# Sheet1.net
KiCad netlist of a schematic drawn in Altium Designer
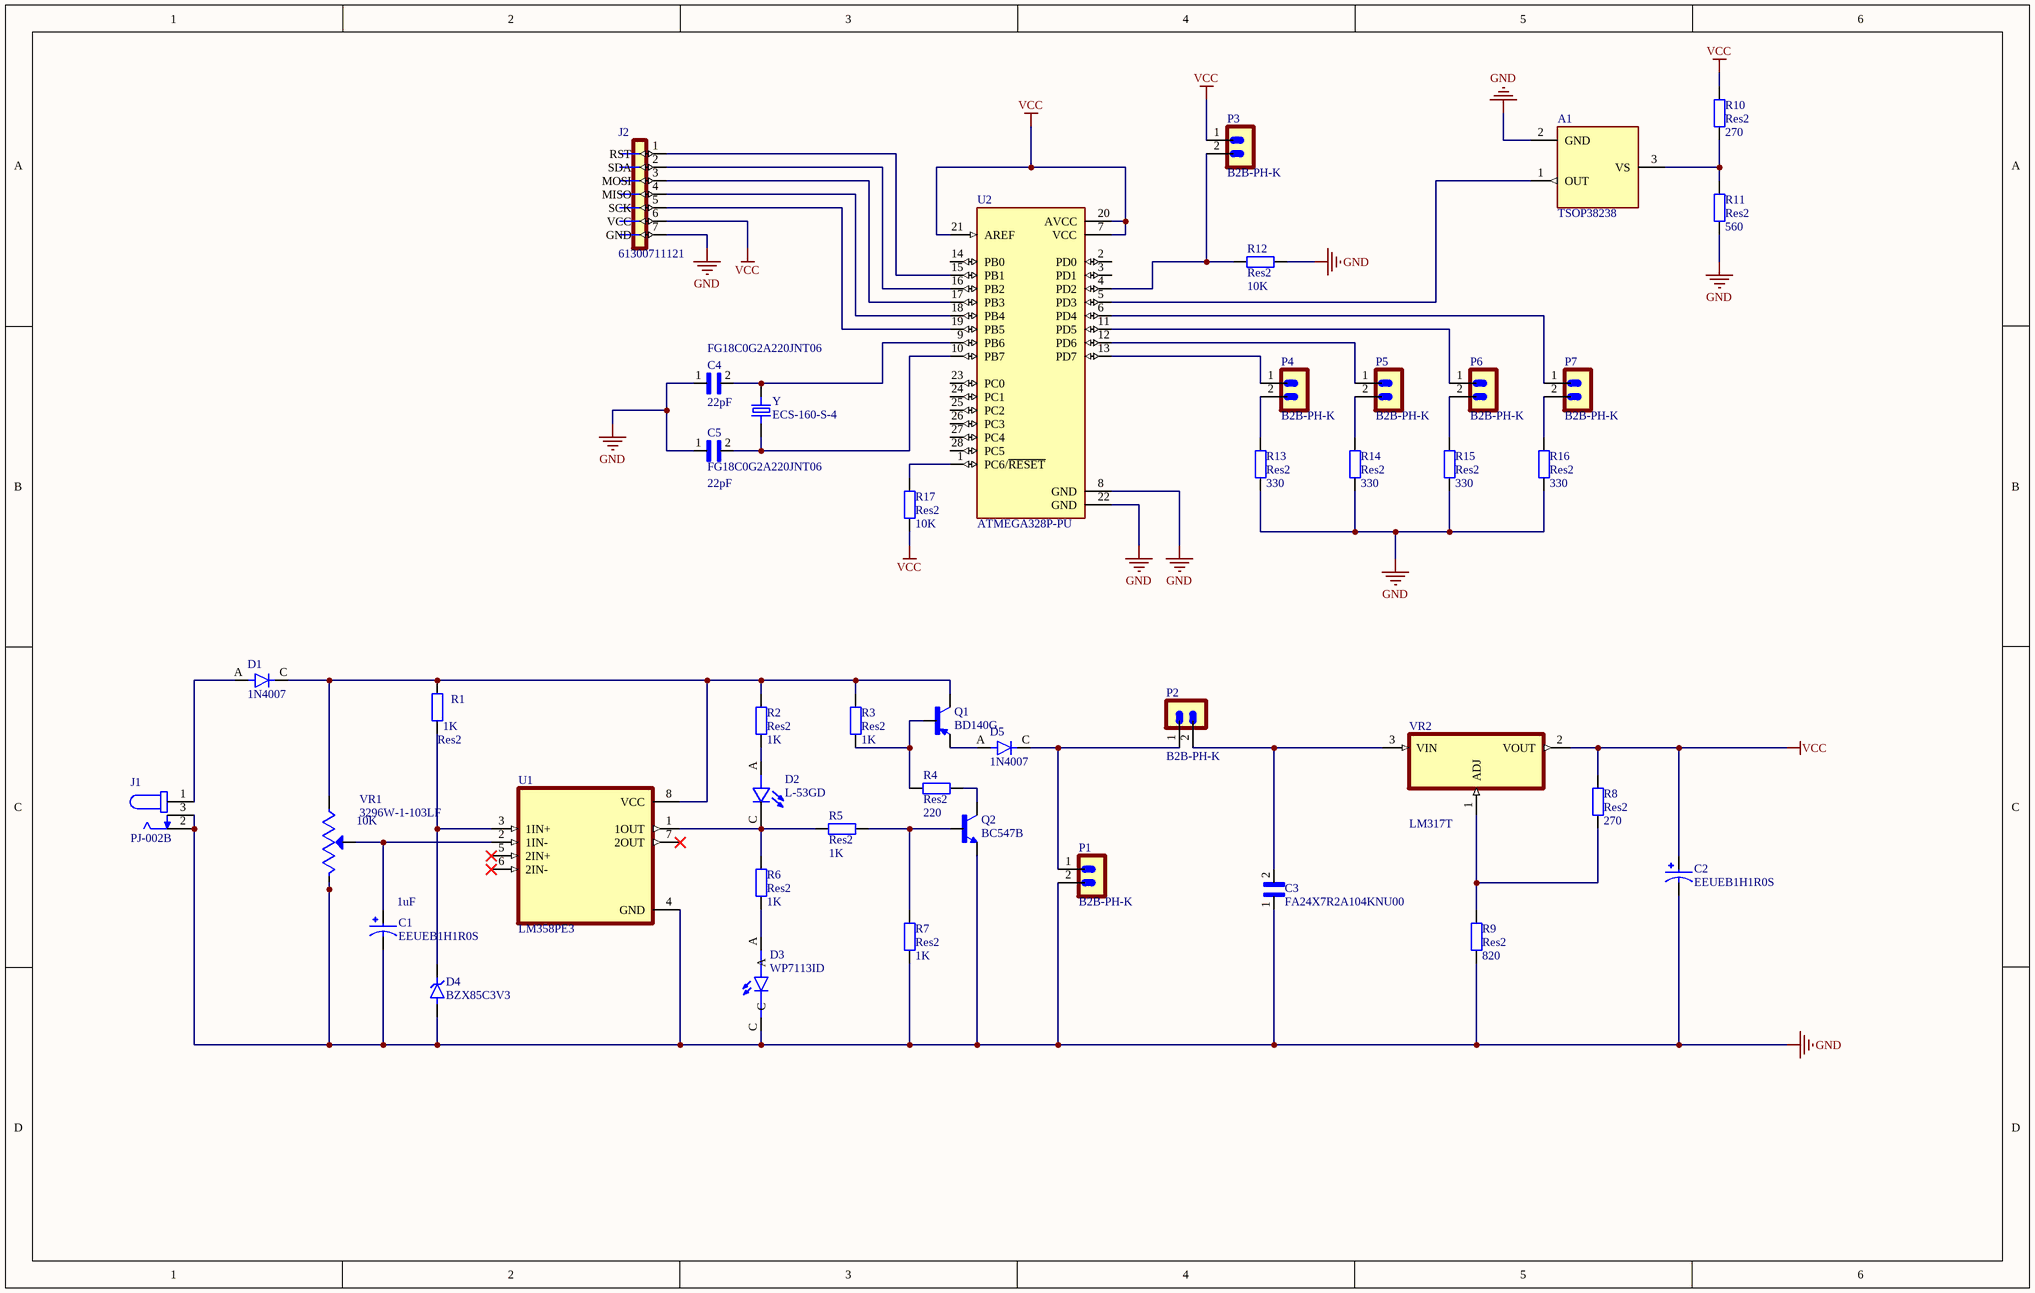
[diagram p0: Sheet1.SchDoc]

(export (version "E")
  (design (tool "Eeschema 10.0.6"))
  (components
    (comp (ref "A1")
      (value "TSOP38238")
      (footprint "XDCR_TSOP38238")
      (description "Remote Receiver Sensor, 38.0kHz 45m")
      (fields (field (name "MF") "Vishay"))
      (libsource (lib "TSOP38238") (part "TSOP38238"))
    )
    (comp (ref "C1")
      (value "EEUEB1H1R0S")
      (footprint "CAPPRD200W50D500H1100")
      (description "CAP ALUM 1UF 20% 50V RADIAL")
      (fields (field (name "ALTIUM_VALUE") "1uF") (field (name "MF") "Panasonic"))
      (libsource (lib "EEUEB1H1R0S") (part "EEUEB1H1R0S"))
    )
    (comp (ref "C2")
      (value "EEUEB1H1R0S")
      (footprint "CAPPRD200W50D500H1100")
      (description "CAP ALUM 1UF 20% 50V RADIAL")
      (fields (field (name "MF") "Panasonic"))
      (libsource (lib "EEUEB1H1R0S") (part "EEUEB1H1R0S"))
    )
    (comp (ref "C3")
      (value "FA24X7R2A104KNU00")
      (footprint "CAPRB500W50L450T300H550")
      (description "0.1 µF ±10% 100V Ceramic Capacitor X7R Radial")
      (fields (field (name "MF") "TDK"))
      (libsource (lib "FA24X7R2A104KNU00") (part "FA24X7R2A104KNU00"))
    )
    (comp (ref "C4")
      (value "FG18C0G2A220JNT06")
      (footprint "CAPRB250W50L400T250H550")
      (description "Cap Ceramic 22pF 100V C0G 5% Radial 2.5mm 125Â°C Ammo")
      (fields
        (field (name "ALTIUM_VALUE") "22pF")
        (field (name "MF") "TDK")
        (field (name "DIGI-KEY_PART_NUMBER") "445-173230-1-ND")
      )
      (libsource (lib "FG18C0G2A220JNT06") (part "FG18C0G2A220JNT06"))
    )
    (comp (ref "C5")
      (value "FG18C0G2A220JNT06")
      (footprint "CAPRB250W50L400T250H550")
      (description "Cap Ceramic 22pF 100V C0G 5% Radial 2.5mm 125Â°C Ammo")
      (fields
        (field (name "ALTIUM_VALUE") "22pF")
        (field (name "MF") "TDK")
        (field (name "DIGI-KEY_PART_NUMBER") "445-173230-1-ND")
      )
      (libsource (lib "FG18C0G2A220JNT06") (part "FG18C0G2A220JNT06"))
    )
    (comp (ref "D1")
      (value "1N4007")
      (footprint "DIOAD1060W80L520D270")
      (description "Diode Standard 1000 V 1A Through Hole DO-41")
      (fields (field (name "MF") "NTE Electronics, Inc."))
      (libsource (lib "1N4007") (part "1N4007"))
    )
    (comp (ref "D2")
      (value "L-53GD")
      (footprint "LEDRD254W50D500H1060")
      (description "LED 5mm Green 568nm 20mcd/10mA 60Â°")
      (fields (field (name "MF") "Kingbright"))
      (libsource (lib "L-53GD") (part "L-53GD"))
    )
    (comp (ref "D3")
      (value "WP7113ID")
      (footprint "LED_WP7113ID")
      (description "Red 617nm LED Indication - Discrete 2V Radial")
      (fields (field (name "MF") "Kingbright"))
      (libsource (lib "WP7113ID") (part "WP7113ID"))
    )
    (comp (ref "D4")
      (value "BZX85C3V3")
      (footprint "DIOAD1036W73L450D282")
      (libsource (lib "BZX85C3V3") (part "BZX85C3V3"))
    )
    (comp (ref "D5")
      (value "1N4007")
      (footprint "DIOAD1060W80L520D270")
      (description "Diode Standard 1000 V 1A Through Hole DO-41")
      (fields (field (name "MF") "NTE Electronics, Inc."))
      (libsource (lib "1N4007") (part "1N4007"))
    )
    (comp (ref "J1")
      (value "PJ-002B")
      (footprint "CUI_PJ-002B")
      (description "2.5 x 6.5 mm, 2.5 A, Horizontal, Through Hole, Dc Power Jack Connector")
      (fields (field (name "MF") "CUI Devices"))
      (libsource (lib "PJ-002B") (part "PJ-002B"))
    )
    (comp (ref "J2")
      (value "61300711121")
      (footprint "1X07-PIN")
      (description "Connector Header Through Hole 7 position 0.100 (2.54mm)")
      (fields (field (name "MF") "Wurth Elektronik"))
      (libsource (lib "61300711121") (part "61300711121"))
    )
    (comp (ref "P1")
      (value "B2B-PH-K")
      (footprint "B2B-PH-K")
      (description "Conn Shrouded Header HDR 2 POS 2mm Solder ST Thru-Hole Box")
      (fields (field (name "MF") "JST Corporation"))
      (libsource (lib "") (part "B2B-PH-K_1"))
    )
    (comp (ref "P2")
      (value "B2B-PH-K")
      (footprint "B2B-PH-K")
      (description "Conn Shrouded Header HDR 2 POS 2mm Solder ST Thru-Hole Box")
      (fields (field (name "MF") "JST Corporation"))
      (libsource (lib "B2B-PH-K") (part "B2B-PH-K"))
    )
    (comp (ref "P3")
      (value "B2B-PH-K")
      (footprint "B2B-PH-K")
      (description "Conn Shrouded Header HDR 2 POS 2mm Solder ST Thru-Hole Box")
      (fields (field (name "MF") "JST Corporation"))
      (libsource (lib "") (part "B2B-PH-K_1"))
    )
    (comp (ref "P4")
      (value "B2B-PH-K")
      (footprint "B2B-PH-K")
      (description "Conn Shrouded Header HDR 2 POS 2mm Solder ST Thru-Hole Box")
      (fields (field (name "MF") "JST Corporation"))
      (libsource (lib "") (part "B2B-PH-K_1"))
    )
    (comp (ref "P5")
      (value "B2B-PH-K")
      (footprint "B2B-PH-K")
      (description "Conn Shrouded Header HDR 2 POS 2mm Solder ST Thru-Hole Box")
      (fields (field (name "MF") "JST Corporation"))
      (libsource (lib "") (part "B2B-PH-K_1"))
    )
    (comp (ref "P6")
      (value "B2B-PH-K")
      (footprint "B2B-PH-K")
      (description "Conn Shrouded Header HDR 2 POS 2mm Solder ST Thru-Hole Box")
      (fields (field (name "MF") "JST Corporation"))
      (libsource (lib "") (part "B2B-PH-K_1"))
    )
    (comp (ref "P7")
      (value "B2B-PH-K")
      (footprint "B2B-PH-K")
      (description "Conn Shrouded Header HDR 2 POS 2mm Solder ST Thru-Hole Box")
      (fields (field (name "MF") "JST Corporation"))
      (libsource (lib "") (part "B2B-PH-K_1"))
    )
    (comp (ref "Q1")
      (value "BD140G")
      (footprint "TO245P780X300X1364-3")
      (description "Bipolar (BJT) Transistor PNP 80 V 1.5 A - 1.25 W Through Hole TO-126")
      (fields (field (name "MF") "ON Semiconductor"))
      (libsource (lib "BD140G") (part "BD140G"))
    )
    (comp (ref "Q2")
      (value "BC547B")
      (footprint "TO92250P510H770-3")
      (description "Bipolar (BJT) TransistÃ¶r NPN 45 V 100 mA 300MHz 625 mW Delikten TO-92 (TO-226)")
      (fields (field (name "MF") "ON Semiconductor"))
      (libsource (lib "BC547B") (part "BC547B"))
    )
    (comp (ref "R1")
      (value "Res2")
      (footprint "AXIAL-0.4")
      (description "Resistor")
      (fields (field (name "ALTIUM_VALUE") "1K") (field (name "PUBLISHER") "Altium Limited"))
      (libsource (lib "Miscellaneous Devices") (part "Res2"))
    )
    (comp (ref "R2")
      (value "Res2")
      (footprint "AXIAL-0.4")
      (description "Resistor")
      (fields (field (name "ALTIUM_VALUE") "1K") (field (name "PUBLISHER") "Altium Limited"))
      (libsource (lib "Miscellaneous Devices") (part "Res2"))
    )
    (comp (ref "R3")
      (value "Res2")
      (footprint "AXIAL-0.4")
      (description "Resistor")
      (fields (field (name "ALTIUM_VALUE") "1K") (field (name "PUBLISHER") "Altium Limited"))
      (libsource (lib "Miscellaneous Devices") (part "Res2"))
    )
    (comp (ref "R4")
      (value "Res2")
      (footprint "AXIAL-0.4")
      (description "Resistor")
      (fields (field (name "ALTIUM_VALUE") "220") (field (name "PUBLISHER") "Altium Limited"))
      (libsource (lib "") (part "Res2_2"))
    )
    (comp (ref "R5")
      (value "Res2")
      (footprint "AXIAL-0.4")
      (description "Resistor")
      (fields (field (name "ALTIUM_VALUE") "1K") (field (name "PUBLISHER") "Altium Limited"))
      (libsource (lib "") (part "Res2_1"))
    )
    (comp (ref "R6")
      (value "Res2")
      (footprint "AXIAL-0.4")
      (description "Resistor")
      (fields (field (name "ALTIUM_VALUE") "1K") (field (name "PUBLISHER") "Altium Limited"))
      (libsource (lib "Miscellaneous Devices") (part "Res2"))
    )
    (comp (ref "R7")
      (value "Res2")
      (footprint "AXIAL-0.4")
      (description "Resistor")
      (fields (field (name "ALTIUM_VALUE") "1K") (field (name "PUBLISHER") "Altium Limited"))
      (libsource (lib "Miscellaneous Devices") (part "Res2"))
    )
    (comp (ref "R8")
      (value "Res2")
      (footprint "AXIAL-0.4")
      (description "Resistor")
      (fields (field (name "ALTIUM_VALUE") "270") (field (name "PUBLISHER") "Altium Limited"))
      (libsource (lib "Miscellaneous Devices") (part "Res2"))
    )
    (comp (ref "R9")
      (value "Res2")
      (footprint "AXIAL-0.4")
      (description "Resistor")
      (fields (field (name "ALTIUM_VALUE") "820") (field (name "PUBLISHER") "Altium Limited"))
      (libsource (lib "Miscellaneous Devices") (part "Res2"))
    )
    (comp (ref "R10")
      (value "Res2")
      (footprint "AXIAL-0.4")
      (description "Resistor")
      (fields (field (name "ALTIUM_VALUE") "270") (field (name "PUBLISHER") "Altium Limited"))
      (libsource (lib "Miscellaneous Devices") (part "Res2"))
    )
    (comp (ref "R11")
      (value "Res2")
      (footprint "AXIAL-0.4")
      (description "Resistor")
      (fields (field (name "ALTIUM_VALUE") "560") (field (name "PUBLISHER") "Altium Limited"))
      (libsource (lib "Miscellaneous Devices") (part "Res2"))
    )
    (comp (ref "R12")
      (value "Res2")
      (footprint "AXIAL-0.4")
      (description "Resistor")
      (fields (field (name "ALTIUM_VALUE") "10K") (field (name "PUBLISHER") "Altium Limited"))
      (libsource (lib "") (part "Res2_1"))
    )
    (comp (ref "R13")
      (value "Res2")
      (footprint "AXIAL-0.4")
      (description "Resistor")
      (fields (field (name "ALTIUM_VALUE") "330") (field (name "PUBLISHER") "Altium Limited"))
      (libsource (lib "Miscellaneous Devices") (part "Res2"))
    )
    (comp (ref "R14")
      (value "Res2")
      (footprint "AXIAL-0.4")
      (description "Resistor")
      (fields (field (name "ALTIUM_VALUE") "330") (field (name "PUBLISHER") "Altium Limited"))
      (libsource (lib "Miscellaneous Devices") (part "Res2"))
    )
    (comp (ref "R15")
      (value "Res2")
      (footprint "AXIAL-0.4")
      (description "Resistor")
      (fields (field (name "ALTIUM_VALUE") "330") (field (name "PUBLISHER") "Altium Limited"))
      (libsource (lib "Miscellaneous Devices") (part "Res2"))
    )
    (comp (ref "R16")
      (value "Res2")
      (footprint "AXIAL-0.4")
      (description "Resistor")
      (fields (field (name "ALTIUM_VALUE") "330") (field (name "PUBLISHER") "Altium Limited"))
      (libsource (lib "Miscellaneous Devices") (part "Res2"))
    )
    (comp (ref "R17")
      (value "Res2")
      (footprint "AXIAL-0.4")
      (description "Resistor")
      (fields (field (name "ALTIUM_VALUE") "10K") (field (name "PUBLISHER") "Altium Limited"))
      (libsource (lib "Miscellaneous Devices") (part "Res2"))
    )
    (comp (ref "U1")
      (value "LM358PE3")
      (footprint "DIP794W45P254L959H508Q8")
      (libsource (lib "LM358PE3") (part "LM358PE3"))
    )
    (comp (ref "U2")
      (value "ATMEGA328P-PU")
      (footprint "DIP794W46P254L2967H457Q28B")
      (description "ATmega Series 20 MHz 32 KB Flash 2 KB SRAM 8-Bit Microcontroller - DIP-28")
      (libsource (lib "ATMEGA328P-PU") (part "ATMEGA328P-PU"))
    )
    (comp (ref "VR1")
      (value "3296W-1-103LF")
      (footprint "TRIM_3296W-1-103LF")
      (description "10 kOhms 0.5W, 1/2W PC Pins Through Hole Trimmer Potentiometer Cermet 25.0 Turn Top Adjustment")
      (fields (field (name "MF") "Bourns") (field (name "ALTIUM_VALUE") "10K"))
      (libsource (lib "3296W-1-103LF") (part "3296W-1-103LF"))
    )
    (comp (ref "VR2")
      (value "LM317T")
      (footprint "TO254P1054X470X1955-3")
      (description "1.5-A, 40-V, adjustable linear voltage regulator 3-TO-220")
      (fields (field (name "MF") "Texas Instruments"))
      (libsource (lib "LM317T") (part "LM317T"))
    )
    (comp (ref "Y")
      (value "ECS-160-S-4")
      (footprint "XTAL_ECS-160-20-4X")
      (description "16MHz Â±30ppm Crystal Series 40 Ohms HC-49/US")
      (fields (field (name "MF") "ECS Inc."))
      (libsource (lib "ECS-160-S-4") (part "ECS-160-S-4"))
    )
  )
  (nets
    (net (code "1") (name "GND") (class "Default")
      (node (ref "A1") (pin "2") (pinfunction "GND_2") (pintype "power_in"))
      (node (ref "C1") (pin "N") (pinfunction "N_N") (pintype "passive"))
      (node (ref "C2") (pin "N") (pinfunction "N_N") (pintype "passive"))
      (node (ref "C3") (pin "1") (pinfunction "1_1") (pintype "passive"))
      (node (ref "C4") (pin "1") (pinfunction "1_1") (pintype "passive"))
      (node (ref "C5") (pin "1") (pinfunction "1_1") (pintype "passive"))
      (node (ref "D3") (pin "C") (pinfunction "C_C") (pintype "passive"))
      (node (ref "D4") (pin "A") (pinfunction "A_A") (pintype "passive"))
      (node (ref "J1") (pin "2") (pinfunction "2_2") (pintype "passive"))
      (node (ref "J1") (pin "3") (pinfunction "3_3") (pintype "passive"))
      (node (ref "J2") (pin "7") (pinfunction "GND_7") (pintype "bidirectional"))
      (node (ref "P1") (pin "2") (pinfunction "2_2") (pintype "passive"))
      (node (ref "Q2") (pin "3") (pinfunction "E_3") (pintype "passive"))
      (node (ref "R11") (pin "1") (pinfunction "1_1") (pintype "passive"))
      (node (ref "R12") (pin "2") (pinfunction "2_2") (pintype "passive"))
      (node (ref "R13") (pin "1") (pinfunction "1_1") (pintype "passive"))
      (node (ref "R14") (pin "1") (pinfunction "1_1") (pintype "passive"))
      (node (ref "R15") (pin "1") (pinfunction "1_1") (pintype "passive"))
      (node (ref "R16") (pin "1") (pinfunction "1_1") (pintype "passive"))
      (node (ref "R7") (pin "1") (pinfunction "1_1") (pintype "passive"))
      (node (ref "R9") (pin "1") (pinfunction "1_1") (pintype "passive"))
      (node (ref "U1") (pin "4") (pinfunction "GND_4") (pintype "power_in"))
      (node (ref "U2") (pin "22") (pinfunction "GND_22") (pintype "power_in"))
      (node (ref "U2") (pin "8") (pinfunction "GND_8") (pintype "power_in"))
      (node (ref "VR1") (pin "3") (pinfunction "CW_3") (pintype "passive"))
    )
    (net (code "2") (name "Net-(A1-OUT)") (class "Default")
      (node (ref "A1") (pin "1") (pinfunction "OUT_1") (pintype "output"))
      (node (ref "U2") (pin "5") (pinfunction "PD3_5") (pintype "bidirectional"))
    )
    (net (code "3") (name "Net-(A1-VS)") (class "Default")
      (node (ref "A1") (pin "3") (pinfunction "VS_3") (pintype "power_in"))
      (node (ref "R10") (pin "1") (pinfunction "1_1") (pintype "passive"))
      (node (ref "R11") (pin "2") (pinfunction "2_2") (pintype "passive"))
    )
    (net (code "4") (name "Net-(D1-PadA)") (class "Default")
      (node (ref "D1") (pin "A") (pinfunction "A_A") (pintype "passive"))
      (node (ref "J1") (pin "1") (pinfunction "1_1") (pintype "passive"))
    )
    (net (code "5") (name "Net-(D2-PadA)") (class "Default")
      (node (ref "D2") (pin "A") (pinfunction "A_A") (pintype "passive"))
      (node (ref "R2") (pin "1") (pinfunction "1_1") (pintype "passive"))
    )
    (net (code "6") (name "Net-(D3-PadA)") (class "Default")
      (node (ref "D3") (pin "A") (pinfunction "A_A") (pintype "passive"))
      (node (ref "R6") (pin "1") (pinfunction "1_1") (pintype "passive"))
    )
    (net (code "7") (name "Net-(D4-K)") (class "Default")
      (node (ref "D4") (pin "C") (pinfunction "K_C") (pintype "passive"))
      (node (ref "R1") (pin "1") (pinfunction "1_1") (pintype "passive"))
      (node (ref "U1") (pin "3") (pinfunction "1IN+_3") (pintype "input"))
    )
    (net (code "8") (name "Net-(D5-PadC)") (class "Default")
      (node (ref "D5") (pin "C") (pinfunction "C_C") (pintype "passive"))
      (node (ref "P1") (pin "1") (pinfunction "1_1") (pintype "passive"))
      (node (ref "P2") (pin "1") (pinfunction "1_1") (pintype "passive"))
    )
    (net (code "9") (name "Net-(J2-MISO)") (class "Default")
      (node (ref "J2") (pin "4") (pinfunction "MISO_4") (pintype "bidirectional"))
      (node (ref "U2") (pin "18") (pinfunction "PB4_18") (pintype "bidirectional"))
    )
    (net (code "10") (name "Net-(J2-MOSI)") (class "Default")
      (node (ref "J2") (pin "3") (pinfunction "MOSI_3") (pintype "bidirectional"))
      (node (ref "U2") (pin "17") (pinfunction "PB3_17") (pintype "bidirectional"))
    )
    (net (code "11") (name "Net-(J2-RST)") (class "Default")
      (node (ref "J2") (pin "1") (pinfunction "RST_1") (pintype "bidirectional"))
      (node (ref "U2") (pin "15") (pinfunction "PB1_15") (pintype "bidirectional"))
    )
    (net (code "12") (name "Net-(J2-SCK)") (class "Default")
      (node (ref "J2") (pin "5") (pinfunction "SCK_5") (pintype "bidirectional"))
      (node (ref "U2") (pin "19") (pinfunction "PB5_19") (pintype "bidirectional"))
    )
    (net (code "13") (name "Net-(J2-SDA)") (class "Default")
      (node (ref "J2") (pin "2") (pinfunction "SDA_2") (pintype "bidirectional"))
      (node (ref "U2") (pin "16") (pinfunction "PB2_16") (pintype "bidirectional"))
    )
    (net (code "14") (name "Net-(P4-Pad2)") (class "Default")
      (node (ref "P4") (pin "2") (pinfunction "2_2") (pintype "passive"))
      (node (ref "R13") (pin "2") (pinfunction "2_2") (pintype "passive"))
    )
    (net (code "15") (name "Net-(P5-Pad2)") (class "Default")
      (node (ref "P5") (pin "2") (pinfunction "2_2") (pintype "passive"))
      (node (ref "R14") (pin "2") (pinfunction "2_2") (pintype "passive"))
    )
    (net (code "16") (name "Net-(P6-Pad2)") (class "Default")
      (node (ref "P6") (pin "2") (pinfunction "2_2") (pintype "passive"))
      (node (ref "R15") (pin "2") (pinfunction "2_2") (pintype "passive"))
    )
    (net (code "17") (name "Net-(P7-Pad2)") (class "Default")
      (node (ref "P7") (pin "2") (pinfunction "2_2") (pintype "passive"))
      (node (ref "R16") (pin "2") (pinfunction "2_2") (pintype "passive"))
    )
    (net (code "18") (name "Net-(Q1-B)") (class "Default")
      (node (ref "Q1") (pin "3") (pinfunction "B_3") (pintype "passive"))
      (node (ref "R3") (pin "1") (pinfunction "1_1") (pintype "passive"))
      (node (ref "R4") (pin "2") (pinfunction "2_2") (pintype "passive"))
    )
    (net (code "19") (name "Net-(Q1-C)") (class "Default")
      (node (ref "D1") (pin "C") (pinfunction "C_C") (pintype "passive"))
      (node (ref "Q1") (pin "2") (pinfunction "C_2") (pintype "passive"))
      (node (ref "R1") (pin "2") (pinfunction "2_2") (pintype "passive"))
      (node (ref "R2") (pin "2") (pinfunction "2_2") (pintype "passive"))
      (node (ref "R3") (pin "2") (pinfunction "2_2") (pintype "passive"))
      (node (ref "U1") (pin "8") (pinfunction "VCC_8") (pintype "power_in"))
      (node (ref "VR1") (pin "1") (pinfunction "CCW_1") (pintype "passive"))
    )
    (net (code "20") (name "Net-(Q1-E)") (class "Default")
      (node (ref "D5") (pin "A") (pinfunction "A_A") (pintype "passive"))
      (node (ref "Q1") (pin "1") (pinfunction "E_1") (pintype "passive"))
    )
    (net (code "21") (name "Net-(Q2-B)") (class "Default")
      (node (ref "Q2") (pin "2") (pinfunction "B_2") (pintype "passive"))
      (node (ref "R5") (pin "2") (pinfunction "2_2") (pintype "passive"))
      (node (ref "R7") (pin "2") (pinfunction "2_2") (pintype "passive"))
    )
    (net (code "22") (name "Net-(Q2-C)") (class "Default")
      (node (ref "Q2") (pin "1") (pinfunction "C_1") (pintype "passive"))
      (node (ref "R4") (pin "1") (pinfunction "1_1") (pintype "passive"))
    )
    (net (code "23") (name "Net-(U1-1IN-)") (class "Default")
      (node (ref "C1") (pin "P") (pinfunction "P_P") (pintype "passive"))
      (node (ref "U1") (pin "2") (pinfunction "1IN-_2") (pintype "input"))
      (node (ref "VR1") (pin "2") (pinfunction "WIPER_2") (pintype "passive"))
    )
    (net (code "24") (name "Net-(U1-1OUT)") (class "Default")
      (node (ref "D2") (pin "C") (pinfunction "C_C") (pintype "passive"))
      (node (ref "R5") (pin "1") (pinfunction "1_1") (pintype "passive"))
      (node (ref "R6") (pin "2") (pinfunction "2_2") (pintype "passive"))
      (node (ref "U1") (pin "1") (pinfunction "1OUT_1") (pintype "output"))
    )
    (net (code "25") (name "Net-(U2-PB6)") (class "Default")
      (node (ref "C4") (pin "2") (pinfunction "2_2") (pintype "passive"))
      (node (ref "U2") (pin "9") (pinfunction "PB6_9") (pintype "bidirectional"))
      (node (ref "Y") (pin "2") (pinfunction "2_2") (pintype "passive"))
    )
    (net (code "26") (name "Net-(U2-PB7)") (class "Default")
      (node (ref "C5") (pin "2") (pinfunction "2_2") (pintype "passive"))
      (node (ref "U2") (pin "10") (pinfunction "PB7_10") (pintype "bidirectional"))
      (node (ref "Y") (pin "1") (pinfunction "1_1") (pintype "passive"))
    )
    (net (code "27") (name "Net-(U2-PC6{slash}~{RESET})") (class "Default")
      (node (ref "R17") (pin "2") (pinfunction "2_2") (pintype "passive"))
      (node (ref "U2") (pin "1") (pinfunction "PC6/~{RESET}_1") (pintype "bidirectional"))
    )
    (net (code "28") (name "Net-(U2-PD2)") (class "Default")
      (node (ref "P3") (pin "2") (pinfunction "2_2") (pintype "passive"))
      (node (ref "R12") (pin "1") (pinfunction "1_1") (pintype "passive"))
      (node (ref "U2") (pin "4") (pinfunction "PD2_4") (pintype "bidirectional"))
    )
    (net (code "29") (name "Net-(U2-PD4)") (class "Default")
      (node (ref "P7") (pin "1") (pinfunction "1_1") (pintype "passive"))
      (node (ref "U2") (pin "6") (pinfunction "PD4_6") (pintype "bidirectional"))
    )
    (net (code "30") (name "Net-(U2-PD5)") (class "Default")
      (node (ref "P6") (pin "1") (pinfunction "1_1") (pintype "passive"))
      (node (ref "U2") (pin "11") (pinfunction "PD5_11") (pintype "bidirectional"))
    )
    (net (code "31") (name "Net-(U2-PD6)") (class "Default")
      (node (ref "P5") (pin "1") (pinfunction "1_1") (pintype "passive"))
      (node (ref "U2") (pin "12") (pinfunction "PD6_12") (pintype "bidirectional"))
    )
    (net (code "32") (name "Net-(U2-PD7)") (class "Default")
      (node (ref "P4") (pin "1") (pinfunction "1_1") (pintype "passive"))
      (node (ref "U2") (pin "13") (pinfunction "PD7_13") (pintype "bidirectional"))
    )
    (net (code "33") (name "Net-(VR2-ADJ)") (class "Default")
      (node (ref "R8") (pin "1") (pinfunction "1_1") (pintype "passive"))
      (node (ref "R9") (pin "2") (pinfunction "2_2") (pintype "passive"))
      (node (ref "VR2") (pin "1") (pinfunction "ADJ_1") (pintype "input"))
    )
    (net (code "34") (name "Net-(VR2-VIN)") (class "Default")
      (node (ref "C3") (pin "2") (pinfunction "2_2") (pintype "passive"))
      (node (ref "P2") (pin "2") (pinfunction "2_2") (pintype "passive"))
      (node (ref "VR2") (pin "3") (pinfunction "VIN_3") (pintype "input"))
    )
    (net (code "35") (name "VCC") (class "Default")
      (node (ref "C2") (pin "P") (pinfunction "P_P") (pintype "passive"))
      (node (ref "J2") (pin "6") (pinfunction "VCC_6") (pintype "bidirectional"))
      (node (ref "P3") (pin "1") (pinfunction "1_1") (pintype "passive"))
      (node (ref "R10") (pin "2") (pinfunction "2_2") (pintype "passive"))
      (node (ref "R17") (pin "1") (pinfunction "1_1") (pintype "passive"))
      (node (ref "R8") (pin "2") (pinfunction "2_2") (pintype "passive"))
      (node (ref "U2") (pin "20") (pinfunction "AVCC_20") (pintype "power_in"))
      (node (ref "U2") (pin "21") (pinfunction "AREF_21") (pintype "input"))
      (node (ref "U2") (pin "7") (pinfunction "VCC_7") (pintype "power_in"))
      (node (ref "VR2") (pin "2") (pinfunction "VOUT_2") (pintype "output"))
    )
    (net (code "36") (name "unconnected-(U1-2IN+-Pad5)") (class "Default")
      (node (ref "U1") (pin "5") (pinfunction "2IN+_5") (pintype "input+no_connect"))
    )
    (net (code "37") (name "unconnected-(U1-2IN--Pad6)") (class "Default")
      (node (ref "U1") (pin "6") (pinfunction "2IN-_6") (pintype "input+no_connect"))
    )
    (net (code "38") (name "unconnected-(U1-2OUT-Pad7)") (class "Default")
      (node (ref "U1") (pin "7") (pinfunction "2OUT_7") (pintype "output+no_connect"))
    )
    (net (code "39") (name "unconnected-(U2-PB0-Pad14)") (class "Default")
      (node (ref "U2") (pin "14") (pinfunction "PB0_14") (pintype "bidirectional"))
    )
    (net (code "40") (name "unconnected-(U2-PC0-Pad23)") (class "Default")
      (node (ref "U2") (pin "23") (pinfunction "PC0_23") (pintype "bidirectional"))
    )
    (net (code "41") (name "unconnected-(U2-PC1-Pad24)") (class "Default")
      (node (ref "U2") (pin "24") (pinfunction "PC1_24") (pintype "bidirectional"))
    )
    (net (code "42") (name "unconnected-(U2-PC2-Pad25)") (class "Default")
      (node (ref "U2") (pin "25") (pinfunction "PC2_25") (pintype "bidirectional"))
    )
    (net (code "43") (name "unconnected-(U2-PC3-Pad26)") (class "Default")
      (node (ref "U2") (pin "26") (pinfunction "PC3_26") (pintype "bidirectional"))
    )
    (net (code "44") (name "unconnected-(U2-PC4-Pad27)") (class "Default")
      (node (ref "U2") (pin "27") (pinfunction "PC4_27") (pintype "bidirectional"))
    )
    (net (code "45") (name "unconnected-(U2-PC5-Pad28)") (class "Default")
      (node (ref "U2") (pin "28") (pinfunction "PC5_28") (pintype "bidirectional"))
    )
    (net (code "46") (name "unconnected-(U2-PD0-Pad2)") (class "Default")
      (node (ref "U2") (pin "2") (pinfunction "PD0_2") (pintype "bidirectional"))
    )
    (net (code "47") (name "unconnected-(U2-PD1-Pad3)") (class "Default")
      (node (ref "U2") (pin "3") (pinfunction "PD1_3") (pintype "bidirectional"))
    )
  )
)
